# Kivipallur_joonis3_toide.net
KiCad netlist of a schematic drawn in Altium Designer
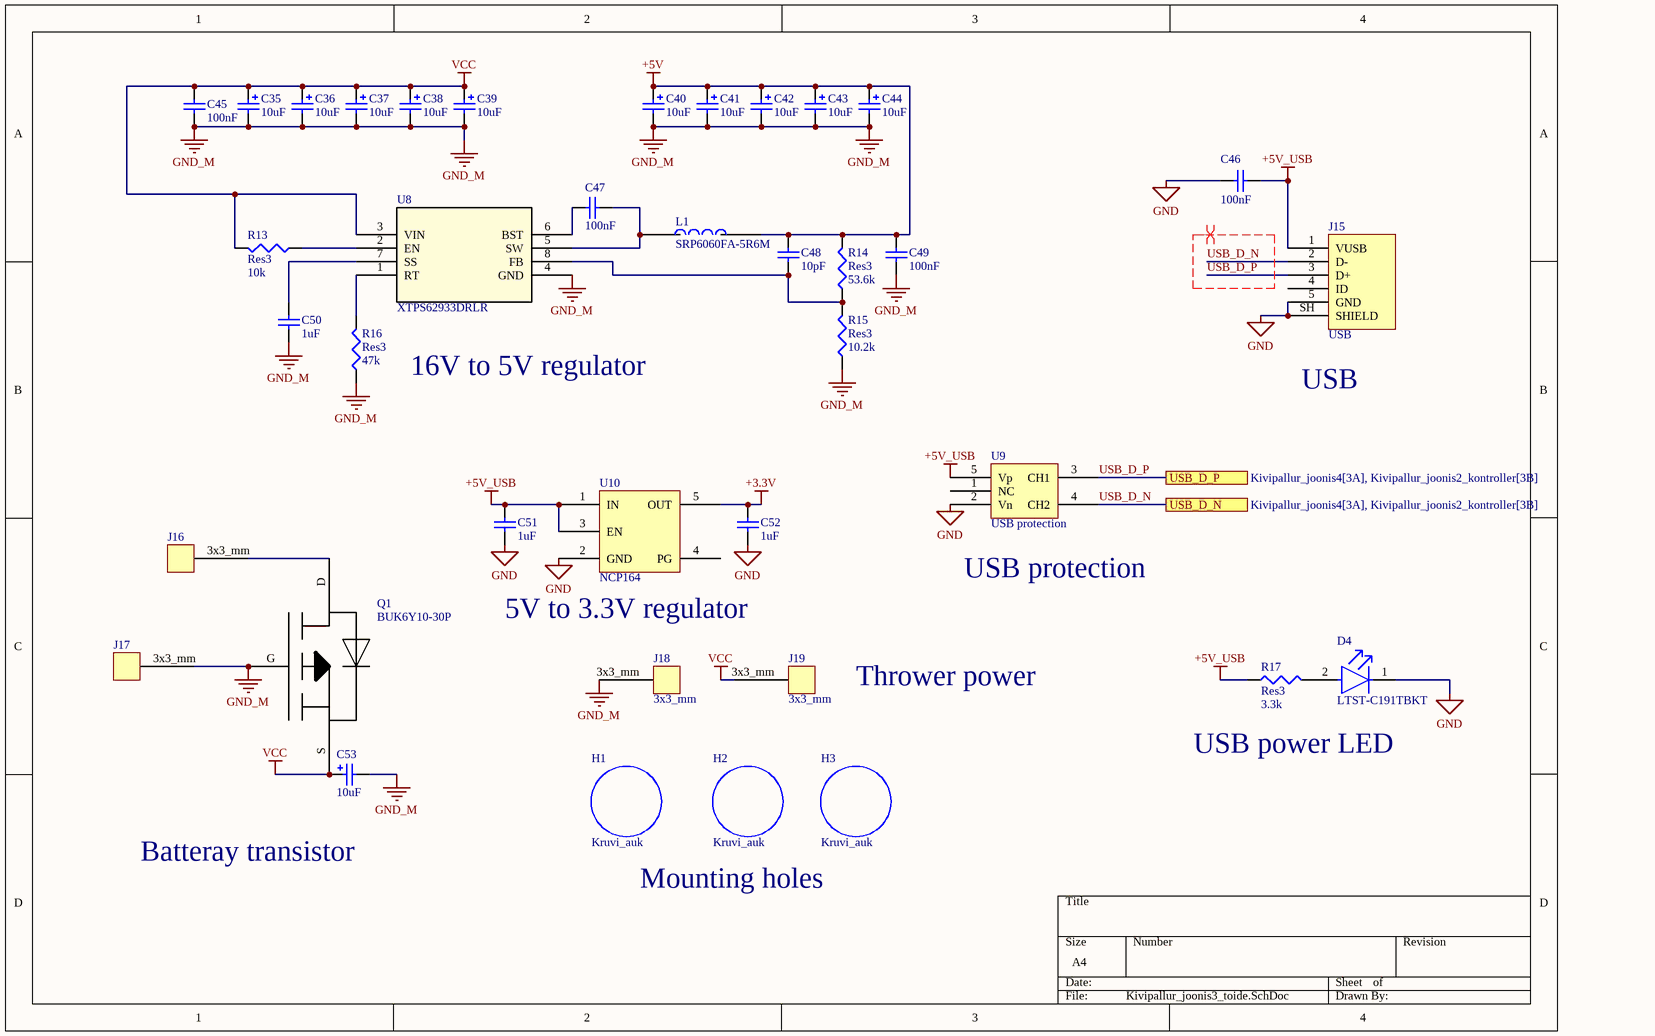
[diagram p0: Kivipallur_joonis3_toide.SchDoc]

(export (version "E")
  (design (tool "Eeschema 10.0.6"))
  (components
    (comp (ref "C35")
      (value "10uF")
      (footprint "C0805")
      (description "Polarized Capacitor (Surface Mount)")
      (fields (field (name "Comment") "Cap Pol3") (field (name "PUBLISHER") "Altium Limited"))
      (libsource (lib "Miscellaneous Devices") (part "Cap Pol3"))
    )
    (comp (ref "C36")
      (value "10uF")
      (footprint "C0805")
      (description "Polarized Capacitor (Surface Mount)")
      (fields (field (name "Comment") "Cap Pol3") (field (name "PUBLISHER") "Altium Limited"))
      (libsource (lib "Miscellaneous Devices") (part "Cap Pol3"))
    )
    (comp (ref "C37")
      (value "10uF")
      (footprint "C0805")
      (description "Polarized Capacitor (Surface Mount)")
      (fields (field (name "Comment") "Cap Pol3") (field (name "PUBLISHER") "Altium Limited"))
      (libsource (lib "Miscellaneous Devices") (part "Cap Pol3"))
    )
    (comp (ref "C38")
      (value "10uF")
      (footprint "C0805")
      (description "Polarized Capacitor (Surface Mount)")
      (fields (field (name "Comment") "Cap Pol3") (field (name "PUBLISHER") "Altium Limited"))
      (libsource (lib "Miscellaneous Devices") (part "Cap Pol3"))
    )
    (comp (ref "C39")
      (value "10uF")
      (footprint "C0805")
      (description "Polarized Capacitor (Surface Mount)")
      (fields (field (name "Comment") "Cap Pol3") (field (name "PUBLISHER") "Altium Limited"))
      (libsource (lib "Miscellaneous Devices") (part "Cap Pol3"))
    )
    (comp (ref "C40")
      (value "10uF")
      (footprint "C0805")
      (description "Polarized Capacitor (Surface Mount)")
      (fields (field (name "Comment") "Cap Pol3") (field (name "PUBLISHER") "Altium Limited"))
      (libsource (lib "Miscellaneous Devices") (part "Cap Pol3"))
    )
    (comp (ref "C41")
      (value "10uF")
      (footprint "C0805")
      (description "Polarized Capacitor (Surface Mount)")
      (fields (field (name "Comment") "Cap Pol3") (field (name "PUBLISHER") "Altium Limited"))
      (libsource (lib "Miscellaneous Devices") (part "Cap Pol3"))
    )
    (comp (ref "C42")
      (value "10uF")
      (footprint "C0805")
      (description "Polarized Capacitor (Surface Mount)")
      (fields (field (name "Comment") "Cap Pol3") (field (name "PUBLISHER") "Altium Limited"))
      (libsource (lib "Miscellaneous Devices") (part "Cap Pol3"))
    )
    (comp (ref "C43")
      (value "10uF")
      (footprint "C0805")
      (description "Polarized Capacitor (Surface Mount)")
      (fields (field (name "Comment") "Cap Pol3") (field (name "PUBLISHER") "Altium Limited"))
      (libsource (lib "Miscellaneous Devices") (part "Cap Pol3"))
    )
    (comp (ref "C44")
      (value "10uF")
      (footprint "C0805")
      (description "Polarized Capacitor (Surface Mount)")
      (fields (field (name "Comment") "Cap Pol3") (field (name "PUBLISHER") "Altium Limited"))
      (libsource (lib "Miscellaneous Devices") (part "Cap Pol3"))
    )
    (comp (ref "C45")
      (value "100nF")
      (footprint "1608[0603]")
      (description "Capacitor (Semiconductor SIM Model)")
      (fields (field (name "Comment") "Cap Semi") (field (name "PUBLISHER") "Altium Limited"))
      (libsource (lib "Miscellaneous Devices") (part "Cap Semi"))
    )
    (comp (ref "C46")
      (value "100nF")
      (footprint "1608[0603]")
      (description "Capacitor (Semiconductor SIM Model)")
      (fields (field (name "Comment") "Cap Semi") (field (name "PUBLISHER") "Altium Limited"))
      (libsource (lib "Miscellaneous Devices") (part "Cap Semi"))
    )
    (comp (ref "C47")
      (value "100nF")
      (footprint "1608[0603]")
      (description "Capacitor (Semiconductor SIM Model)")
      (fields (field (name "Comment") "Cap Semi") (field (name "PUBLISHER") "Altium Limited"))
      (libsource (lib "Miscellaneous Devices") (part "Cap Semi"))
    )
    (comp (ref "C48")
      (value "10pF")
      (footprint "1608[0603]")
      (description "Capacitor (Semiconductor SIM Model)")
      (fields (field (name "Comment") "Cap Semi") (field (name "PUBLISHER") "Altium Limited"))
      (libsource (lib "Miscellaneous Devices") (part "Cap Semi"))
    )
    (comp (ref "C49")
      (value "100nF")
      (footprint "1608[0603]")
      (description "Capacitor (Semiconductor SIM Model)")
      (fields (field (name "Comment") "Cap Semi") (field (name "PUBLISHER") "Altium Limited"))
      (libsource (lib "Miscellaneous Devices") (part "Cap Semi"))
    )
    (comp (ref "C50")
      (value "1uF")
      (footprint "1608[0603]")
      (description "Capacitor (Semiconductor SIM Model)")
      (fields (field (name "Comment") "Cap Semi") (field (name "PUBLISHER") "Altium Limited"))
      (libsource (lib "Miscellaneous Devices") (part "Cap Semi"))
    )
    (comp (ref "C51")
      (value "1uF")
      (footprint "1608[0603]")
      (description "Capacitor (Semiconductor SIM Model)")
      (fields (field (name "Comment") "Cap Semi") (field (name "PUBLISHER") "Altium Limited"))
      (libsource (lib "Miscellaneous Devices") (part "Cap Semi"))
    )
    (comp (ref "C52")
      (value "1uF")
      (footprint "1608[0603]")
      (description "Capacitor (Semiconductor SIM Model)")
      (fields (field (name "Comment") "Cap Semi") (field (name "PUBLISHER") "Altium Limited"))
      (libsource (lib "Miscellaneous Devices") (part "Cap Semi"))
    )
    (comp (ref "C53")
      (value "10uF")
      (footprint "C0805")
      (description "Polarized Capacitor (Surface Mount)")
      (fields (field (name "Comment") "Cap Pol3") (field (name "PUBLISHER") "Altium Limited"))
      (libsource (lib "Miscellaneous Devices") (part "Cap Pol3"))
    )
    (comp (ref "D4")
      (value "LTST-C191TBKT")
      (footprint "FP-LTST-C191TBKT-MFG")
      (description "LED BLUE CLEAR CHIP SMD")
      (libsource (lib "Altium Content Vault") (part "8706943c75ba83719d021d2fdc84c58"))
    )
    (comp (ref "H1")
      (value "Kruvi_auk")
      (footprint "kruvi_auk")
      (libsource (lib "kruvi_auk") (part "Kruvi_auk"))
    )
    (comp (ref "H2")
      (value "Kruvi_auk")
      (footprint "kruvi_auk")
      (libsource (lib "kruvi_auk") (part "Kruvi_auk"))
    )
    (comp (ref "H3")
      (value "Kruvi_auk")
      (footprint "kruvi_auk")
      (libsource (lib "kruvi_auk") (part "Kruvi_auk"))
    )
    (comp (ref "J15") (value "USB") (footprint "USB") (libsource (lib "USB_m") (part "USB")))
    (comp (ref "J16") (value "3x3_mm") (footprint "3x3_mm") (libsource (lib "3x3_mm") (part "3x3_mm")))
    (comp (ref "J17") (value "3x3_mm") (footprint "3x3_mm") (libsource (lib "3x3_mm") (part "3x3_mm")))
    (comp (ref "J18") (value "3x3_mm") (footprint "3x3_mm") (libsource (lib "") (part "3x3_mm_1")))
    (comp (ref "J19") (value "3x3_mm") (footprint "3x3_mm") (libsource (lib "") (part "3x3_mm_1")))
    (comp (ref "L1")
      (value "SRP6060FA-5R6M")
      (footprint "test alus")
      (libsource (lib "SRP6060FA-5R6M") (part "SRP6060FA-5R6M"))
    )
    (comp (ref "Q1")
      (value "BUK6Y10-30P")
      (footprint "BUK6Y10-30P")
      (libsource (lib "BUK6Y10-30P") (part "BUK6Y10-30P"))
    )
    (comp (ref "R13")
      (value "Res3")
      (footprint "J1-0603")
      (description "Resistor")
      (fields (field (name "ALTIUM_VALUE") "10k") (field (name "PUBLISHER") "Altium Limited"))
      (libsource (lib "Miscellaneous Devices") (part "Res3"))
    )
    (comp (ref "R14")
      (value "Res3")
      (footprint "J1-0603")
      (description "Resistor")
      (fields (field (name "ALTIUM_VALUE") "53.6k") (field (name "PUBLISHER") "Altium Limited"))
      (libsource (lib "Miscellaneous Devices") (part "Res3"))
    )
    (comp (ref "R15")
      (value "Res3")
      (footprint "J1-0603")
      (description "Resistor")
      (fields (field (name "ALTIUM_VALUE") "10.2k") (field (name "PUBLISHER") "Altium Limited"))
      (libsource (lib "Miscellaneous Devices") (part "Res3"))
    )
    (comp (ref "R16")
      (value "Res3")
      (footprint "J1-0603")
      (description "Resistor")
      (fields (field (name "ALTIUM_VALUE") "47k") (field (name "PUBLISHER") "Altium Limited"))
      (libsource (lib "Miscellaneous Devices") (part "Res3"))
    )
    (comp (ref "R17")
      (value "Res3")
      (footprint "J1-0603")
      (description "Resistor")
      (fields (field (name "ALTIUM_VALUE") "3.3k") (field (name "PUBLISHER") "Altium Limited"))
      (libsource (lib "Miscellaneous Devices") (part "Res3"))
    )
    (comp (ref "U8")
      (value "XTPS62933DRLR")
      (footprint "SOT_33DRLR_TEX")
      (description "No Description Available")
      (fields (field (name "COPYRIGHT") "Copyright (C) 2022 Ultra Librarian. All rights reserved."))
      (libsource (lib "XTPS62933DRLR") (part "XTPS62933DRLR"))
    )
    (comp (ref "U9")
      (value "USB protection")
      (footprint "USB_PROTECTION_3")
      (libsource (lib "USB_protection") (part "USB protection"))
    )
    (comp (ref "U10") (value "NCP164") (footprint "NCP164_2") (libsource (lib "NCP164_") (part "NCP164")))
  )
  (nets
    (net (code "1") (name "+3.3V") (class "Default")
      (node (ref "C52") (pin "1") (pinfunction "1_1") (pintype "passive"))
      (node (ref "U10") (pin "5") (pinfunction "OUT_5") (pintype "power_in"))
    )
    (net (code "2") (name "+5V") (class "Default")
      (node (ref "C40") (pin "1") (pinfunction "1_1") (pintype "passive"))
      (node (ref "C41") (pin "1") (pinfunction "1_1") (pintype "passive"))
      (node (ref "C42") (pin "1") (pinfunction "1_1") (pintype "passive"))
      (node (ref "C43") (pin "1") (pinfunction "1_1") (pintype "passive"))
      (node (ref "C44") (pin "1") (pinfunction "1_1") (pintype "passive"))
      (node (ref "C48") (pin "1") (pinfunction "1_1") (pintype "passive"))
      (node (ref "C49") (pin "1") (pinfunction "1_1") (pintype "passive"))
      (node (ref "L1") (pin "2") (pinfunction "2_2") (pintype "passive"))
      (node (ref "R14") (pin "2") (pinfunction "2_2") (pintype "passive"))
    )
    (net (code "3") (name "+5V_USB") (class "Default")
      (node (ref "C46") (pin "1") (pinfunction "1_1") (pintype "passive"))
      (node (ref "C51") (pin "1") (pinfunction "1_1") (pintype "passive"))
      (node (ref "J15") (pin "1") (pinfunction "VUSB_1") (pintype "passive"))
      (node (ref "R17") (pin "1") (pinfunction "1_1") (pintype "passive"))
      (node (ref "U10") (pin "1") (pinfunction "IN_1") (pintype "power_in"))
      (node (ref "U10") (pin "3") (pinfunction "EN_3") (pintype "passive"))
      (node (ref "U9") (pin "5") (pinfunction "Vp_5") (pintype "passive"))
    )
    (net (code "4") (name "/USB_D_N") (class "Default")
      (node (ref "J15") (pin "2") (pinfunction "D-_2") (pintype "passive"))
      (node (ref "U9") (pin "4") (pinfunction "CH2_4") (pintype "passive"))
    )
    (net (code "5") (name "/USB_D_P") (class "Default")
      (node (ref "J15") (pin "3") (pinfunction "D+_3") (pintype "passive"))
      (node (ref "U9") (pin "3") (pinfunction "CH1_3") (pintype "passive"))
    )
    (net (code "6") (name "GND") (class "Default")
      (node (ref "C46") (pin "2") (pinfunction "2_2") (pintype "passive"))
      (node (ref "C51") (pin "2") (pinfunction "2_2") (pintype "passive"))
      (node (ref "C52") (pin "2") (pinfunction "2_2") (pintype "passive"))
      (node (ref "D4") (pin "1") (pinfunction "C_1") (pintype "passive"))
      (node (ref "J15") (pin "5") (pinfunction "GND_5") (pintype "passive"))
      (node (ref "J15") (pin "SH") (pinfunction "SHIELD_SH") (pintype "passive"))
      (node (ref "U10") (pin "2") (pinfunction "GND_2") (pintype "power_in"))
      (node (ref "U9") (pin "2") (pinfunction "Vn_2") (pintype "passive"))
    )
    (net (code "7") (name "GND_M") (class "Default")
      (node (ref "C35") (pin "2") (pinfunction "2_2") (pintype "passive"))
      (node (ref "C36") (pin "2") (pinfunction "2_2") (pintype "passive"))
      (node (ref "C37") (pin "2") (pinfunction "2_2") (pintype "passive"))
      (node (ref "C38") (pin "2") (pinfunction "2_2") (pintype "passive"))
      (node (ref "C39") (pin "2") (pinfunction "2_2") (pintype "passive"))
      (node (ref "C40") (pin "2") (pinfunction "2_2") (pintype "passive"))
      (node (ref "C41") (pin "2") (pinfunction "2_2") (pintype "passive"))
      (node (ref "C42") (pin "2") (pinfunction "2_2") (pintype "passive"))
      (node (ref "C43") (pin "2") (pinfunction "2_2") (pintype "passive"))
      (node (ref "C44") (pin "2") (pinfunction "2_2") (pintype "passive"))
      (node (ref "C45") (pin "2") (pinfunction "2_2") (pintype "passive"))
      (node (ref "C49") (pin "2") (pinfunction "2_2") (pintype "passive"))
      (node (ref "C50") (pin "2") (pinfunction "2_2") (pintype "passive"))
      (node (ref "C53") (pin "2") (pinfunction "2_2") (pintype "passive"))
      (node (ref "J17") (pin "3x3_mm") (pintype "power_in"))
      (node (ref "J18") (pin "3x3_mm") (pintype "power_in"))
      (node (ref "Q1") (pin "G") (pintype "passive"))
      (node (ref "R15") (pin "1") (pinfunction "1_1") (pintype "passive"))
      (node (ref "R16") (pin "1") (pinfunction "1_1") (pintype "passive"))
      (node (ref "U8") (pin "4") (pinfunction "GND_4") (pintype "passive"))
    )
    (net (code "8") (name "Net-(D4-A)") (class "Default")
      (node (ref "D4") (pin "2") (pinfunction "A_2") (pintype "passive"))
      (node (ref "R17") (pin "2") (pinfunction "2_2") (pintype "passive"))
    )
    (net (code "9") (name "Net-(J16-Pad3x3_mm)") (class "Default")
      (node (ref "J16") (pin "3x3_mm") (pintype "power_in"))
      (node (ref "Q1") (pin "D") (pintype "passive"))
    )
    (net (code "10") (name "Net-(U8-BST)") (class "Default")
      (node (ref "C47") (pin "1") (pinfunction "1_1") (pintype "passive"))
      (node (ref "U8") (pin "6") (pinfunction "BST_6") (pintype "passive"))
    )
    (net (code "11") (name "Net-(U8-EN)") (class "Default")
      (node (ref "R13") (pin "1") (pinfunction "1_1") (pintype "passive"))
      (node (ref "U8") (pin "2") (pinfunction "EN_2") (pintype "passive"))
    )
    (net (code "12") (name "Net-(U8-FB)") (class "Default")
      (node (ref "C48") (pin "2") (pinfunction "2_2") (pintype "passive"))
      (node (ref "R14") (pin "1") (pinfunction "1_1") (pintype "passive"))
      (node (ref "R15") (pin "2") (pinfunction "2_2") (pintype "passive"))
      (node (ref "U8") (pin "8") (pinfunction "FB_8") (pintype "passive"))
    )
    (net (code "13") (name "Net-(U8-RT)") (class "Default")
      (node (ref "R16") (pin "2") (pinfunction "2_2") (pintype "passive"))
      (node (ref "U8") (pin "1") (pinfunction "RT_1") (pintype "passive"))
    )
    (net (code "14") (name "Net-(U8-SS)") (class "Default")
      (node (ref "C50") (pin "1") (pinfunction "1_1") (pintype "passive"))
      (node (ref "U8") (pin "7") (pinfunction "SS_7") (pintype "passive"))
    )
    (net (code "15") (name "Net-(U8-SW)") (class "Default")
      (node (ref "C47") (pin "2") (pinfunction "2_2") (pintype "passive"))
      (node (ref "L1") (pin "1") (pinfunction "1_1") (pintype "passive"))
      (node (ref "U8") (pin "5") (pinfunction "SW_5") (pintype "passive"))
    )
    (net (code "16") (name "VCC") (class "Default")
      (node (ref "C35") (pin "1") (pinfunction "1_1") (pintype "passive"))
      (node (ref "C36") (pin "1") (pinfunction "1_1") (pintype "passive"))
      (node (ref "C37") (pin "1") (pinfunction "1_1") (pintype "passive"))
      (node (ref "C38") (pin "1") (pinfunction "1_1") (pintype "passive"))
      (node (ref "C39") (pin "1") (pinfunction "1_1") (pintype "passive"))
      (node (ref "C45") (pin "1") (pinfunction "1_1") (pintype "passive"))
      (node (ref "C53") (pin "1") (pinfunction "1_1") (pintype "passive"))
      (node (ref "J19") (pin "3x3_mm") (pintype "power_in"))
      (node (ref "Q1") (pin "S") (pintype "passive"))
      (node (ref "R13") (pin "2") (pinfunction "2_2") (pintype "passive"))
      (node (ref "U8") (pin "3") (pinfunction "VIN_3") (pintype "passive"))
    )
    (net (code "17") (name "unconnected-(J15-ID-Pad4)") (class "Default")
      (node (ref "J15") (pin "4") (pinfunction "ID_4") (pintype "passive"))
    )
    (net (code "18") (name "unconnected-(U9-NC-Pad1)") (class "Default")
      (node (ref "U9") (pin "1") (pinfunction "NC_1") (pintype "passive"))
    )
    (net (code "19") (name "unconnected-(U10-PG-Pad4)") (class "Default")
      (node (ref "U10") (pin "4") (pinfunction "PG_4") (pintype "passive"))
    )
  )
)
